# Level_Shifter_V1_0.net
KiCad netlist of a schematic drawn in Altium Designer
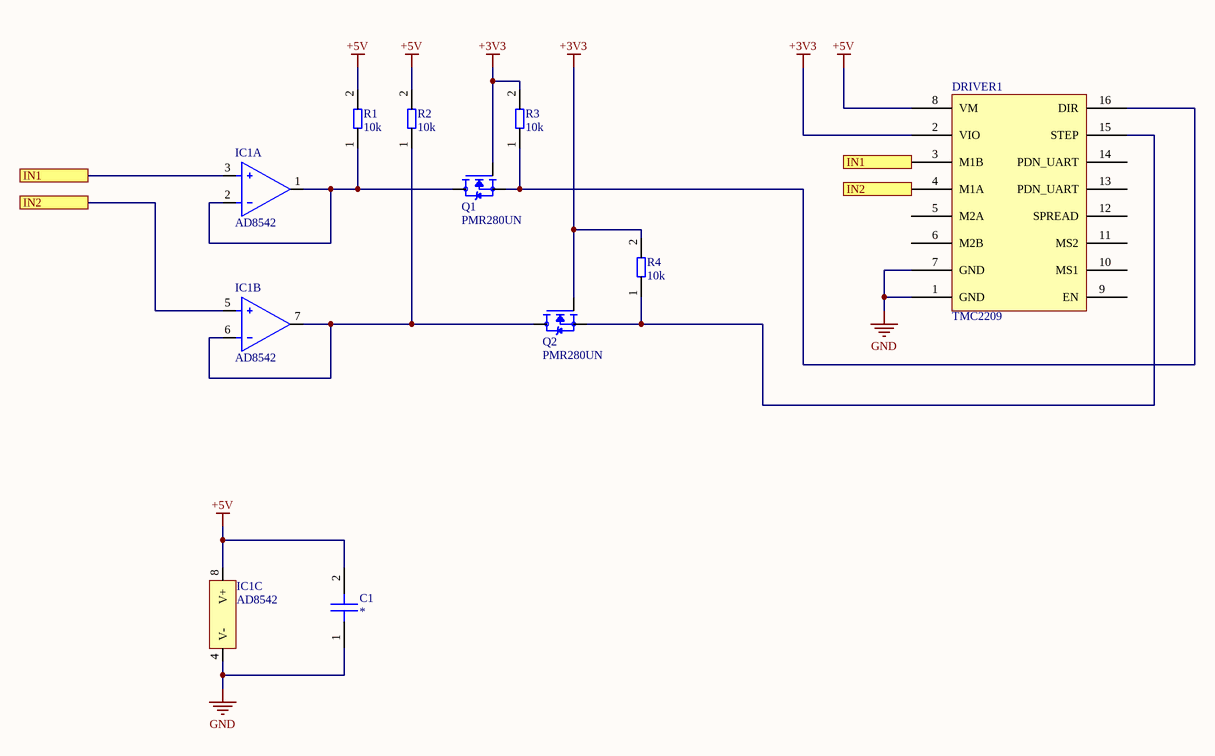
[diagram p0: Level Shifter V1.0.SchDoc]

(export (version "E")
  (design (tool "Eeschema 10.0.6"))
  (components
    (comp (ref "C1")
      (value "*")
      (footprint "0805 Resistor - IPC A")
      (libsource (lib "Radolovic_SCH_Library") (part "CAP_0805_generic"))
    )
    (comp (ref "DRIVER1")
      (value "TMC2209")
      (footprint "TMC2209")
      (description "TMC2209 FET based stepper motor driver board")
      (libsource (lib "Radolovic_SCH_Library") (part "TMC2209"))
    )
    (comp (ref "IC1")
      (value "AD8542")
      (footprint "IC_AD8542ARMZ_Analog_Devices")
      (description "Operational Amplifiers - Op Amps DUAL, LOW PWR RAIL/RAIL OP AMP\r\nAD8542ARZ\r\nSOIC-8")
      (libsource (lib "Radolovic_SCH_Library") (part "IC_AD8542_ANALOG"))
    )
    (comp (ref "Q1")
      (value "PMR280UN")
      (footprint "MOSFET_PMR280UN_NEXPERIA")
      (libsource (lib "Radolovic_SCH_Library") (part "MOSFET_PMR280UN_NEXPERIA"))
    )
    (comp (ref "Q2")
      (value "PMR280UN")
      (footprint "MOSFET_PMR280UN_NEXPERIA")
      (libsource (lib "Radolovic_SCH_Library") (part "MOSFET_PMR280UN_NEXPERIA"))
    )
    (comp (ref "R1")
      (value "10k")
      (footprint "0805 Resistor - IPC A")
      (libsource (lib "Radolovic_SCH_Library") (part "RES_0805_generic"))
    )
    (comp (ref "R2")
      (value "10k")
      (footprint "0805 Resistor - IPC A")
      (libsource (lib "Radolovic_SCH_Library") (part "RES_0805_generic"))
    )
    (comp (ref "R3")
      (value "10k")
      (footprint "0805 Resistor - IPC A")
      (libsource (lib "Radolovic_SCH_Library") (part "RES_0805_generic"))
    )
    (comp (ref "R4")
      (value "10k")
      (footprint "0805 Resistor - IPC A")
      (libsource (lib "Radolovic_SCH_Library") (part "RES_0805_generic"))
    )
  )
  (nets
    (net (code "1") (name "+3V3") (class "Default")
      (node (ref "DRIVER1") (pin "2") (pinfunction "VIO_2") (pintype "passive"))
      (node (ref "Q1") (pin "1") (pinfunction "G_1") (pintype "passive"))
      (node (ref "Q2") (pin "1") (pinfunction "G_1") (pintype "passive"))
      (node (ref "R3") (pin "2") (pintype "passive"))
      (node (ref "R4") (pin "2") (pintype "passive"))
    )
    (net (code "2") (name "+5V") (class "Default")
      (node (ref "C1") (pin "2") (pintype "passive"))
      (node (ref "DRIVER1") (pin "8") (pinfunction "VM_8") (pintype "passive"))
      (node (ref "IC1") (pin "8") (pinfunction "V+_8") (pintype "passive"))
      (node (ref "R1") (pin "2") (pintype "passive"))
      (node (ref "R2") (pin "2") (pintype "passive"))
    )
    (net (code "3") (name "/IN1") (class "Default")
      (node (ref "DRIVER1") (pin "3") (pinfunction "M1B_3") (pintype "passive"))
      (node (ref "IC1") (pin "3") (pinfunction "V_IN_A+_3") (pintype "passive"))
    )
    (net (code "4") (name "/IN2") (class "Default")
      (node (ref "DRIVER1") (pin "4") (pinfunction "M1A_4") (pintype "passive"))
      (node (ref "IC1") (pin "5") (pinfunction "V_IN_B+_5") (pintype "passive"))
    )
    (net (code "5") (name "GND") (class "Default")
      (node (ref "C1") (pin "1") (pintype "passive"))
      (node (ref "DRIVER1") (pin "1") (pinfunction "GND_1") (pintype "passive"))
      (node (ref "DRIVER1") (pin "7") (pinfunction "GND_7") (pintype "passive"))
      (node (ref "IC1") (pin "4") (pinfunction "V-_4") (pintype "passive"))
    )
    (net (code "6") (name "Net-(DRIVER1-DIR)") (class "Default")
      (node (ref "DRIVER1") (pin "16") (pinfunction "DIR_16") (pintype "passive"))
      (node (ref "Q1") (pin "2") (pinfunction "S_2") (pintype "passive"))
      (node (ref "R3") (pin "1") (pintype "passive"))
    )
    (net (code "7") (name "Net-(DRIVER1-STEP)") (class "Default")
      (node (ref "DRIVER1") (pin "15") (pinfunction "STEP_15") (pintype "passive"))
      (node (ref "Q2") (pin "2") (pinfunction "S_2") (pintype "passive"))
      (node (ref "R4") (pin "1") (pintype "passive"))
    )
    (net (code "8") (name "Net-(IC1A-OUT_A)") (class "Default")
      (node (ref "IC1") (pin "1") (pinfunction "OUT_A_1") (pintype "passive"))
      (node (ref "IC1") (pin "2") (pinfunction "V_IN_A-_2") (pintype "passive"))
      (node (ref "Q1") (pin "3") (pinfunction "D_3") (pintype "passive"))
      (node (ref "R1") (pin "1") (pintype "passive"))
    )
    (net (code "9") (name "Net-(IC1B-OUT_B)") (class "Default")
      (node (ref "IC1") (pin "6") (pinfunction "V_IN_B-_6") (pintype "passive"))
      (node (ref "IC1") (pin "7") (pinfunction "OUT_B_7") (pintype "passive"))
      (node (ref "Q2") (pin "3") (pinfunction "D_3") (pintype "passive"))
      (node (ref "R2") (pin "1") (pintype "passive"))
    )
    (net (code "10") (name "unconnected-(DRIVER1-EN-Pad9)") (class "Default")
      (node (ref "DRIVER1") (pin "9") (pinfunction "EN_9") (pintype "passive"))
    )
    (net (code "11") (name "unconnected-(DRIVER1-M2A-Pad5)") (class "Default")
      (node (ref "DRIVER1") (pin "5") (pinfunction "M2A_5") (pintype "passive"))
    )
    (net (code "12") (name "unconnected-(DRIVER1-M2B-Pad6)") (class "Default")
      (node (ref "DRIVER1") (pin "6") (pinfunction "M2B_6") (pintype "passive"))
    )
    (net (code "13") (name "unconnected-(DRIVER1-MS1-Pad10)") (class "Default")
      (node (ref "DRIVER1") (pin "10") (pinfunction "MS1_10") (pintype "passive"))
    )
    (net (code "14") (name "unconnected-(DRIVER1-MS2-Pad11)") (class "Default")
      (node (ref "DRIVER1") (pin "11") (pinfunction "MS2_11") (pintype "passive"))
    )
    (net (code "15") (name "unconnected-(DRIVER1-PDN_UART-Pad13)") (class "Default")
      (node (ref "DRIVER1") (pin "13") (pinfunction "PDN_UART_13") (pintype "passive"))
    )
    (net (code "16") (name "unconnected-(DRIVER1-PDN_UART-Pad14)") (class "Default")
      (node (ref "DRIVER1") (pin "14") (pinfunction "PDN_UART_14") (pintype "passive"))
    )
    (net (code "17") (name "unconnected-(DRIVER1-SPREAD-Pad12)") (class "Default")
      (node (ref "DRIVER1") (pin "12") (pinfunction "SPREAD_12") (pintype "passive"))
    )
  )
)
